# 08_-_Microcontroller.net
KiCad netlist of a schematic drawn in Altium Designer
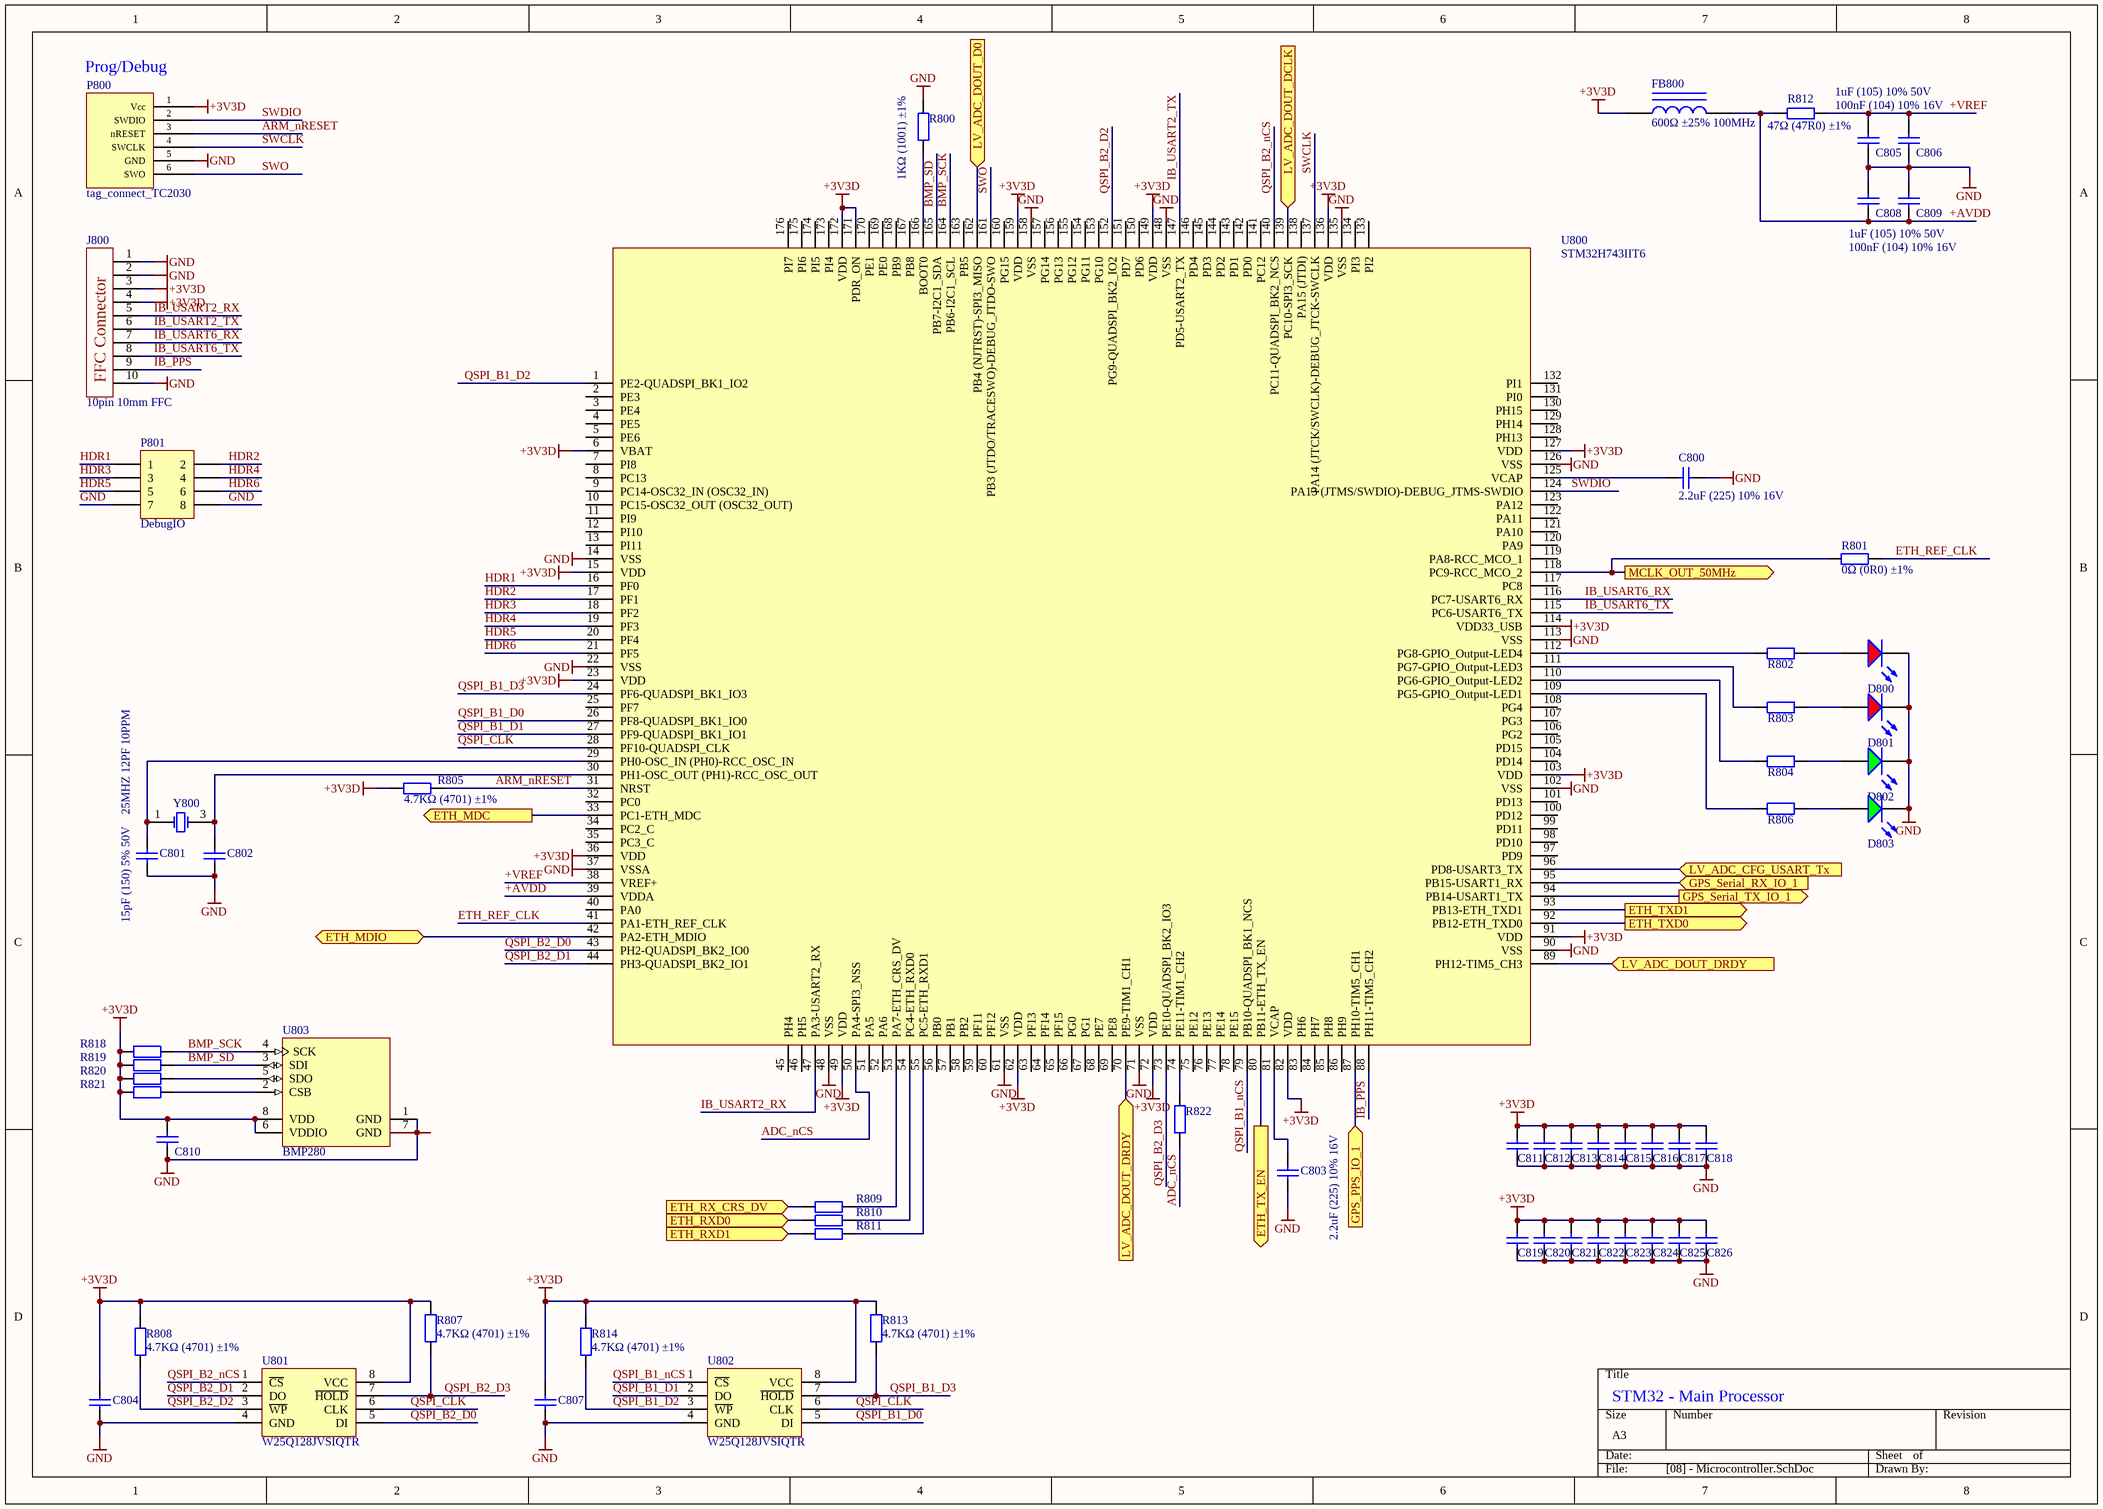
[diagram p0: [08] - Microcontroller.SchDoc]

(export (version "E")
  (design (tool "Eeschema 10.0.6"))
  (components
    (comp (ref "C800")
      (value "2.2uF (225) 10% 16V")
      (footprint "0603_C")
      (description "贴片电容")
      (libsource (lib "Cap") (part "0603 2.2uF (225) 10% 16V"))
    )
    (comp (ref "C801")
      (value "15pF (150) 5% 50V")
      (footprint "0402_C")
      (description "贴片电容")
      (libsource (lib "Cap") (part "0402 15pF (150) 5% 50V"))
    )
    (comp (ref "C802")
      (value "15pF (150) 5% 50V")
      (footprint "0402_C")
      (description "贴片电容")
      (libsource (lib "Cap") (part "0402 15pF (150) 5% 50V"))
    )
    (comp (ref "C803")
      (value "2.2uF (225) 10% 16V")
      (footprint "0603_C")
      (description "贴片电容")
      (libsource (lib "Cap") (part "0603 2.2uF (225) 10% 16V"))
    )
    (comp (ref "C804")
      (value "100nF (104) 10% 16V")
      (footprint "0402_C")
      (description "贴片电容")
      (libsource (lib "Cap") (part "0402 100nF (104) 10% 16V"))
    )
    (comp (ref "C805")
      (value "1uF (105) 10% 50V")
      (footprint "0603_C")
      (description "贴片电容")
      (libsource (lib "Cap") (part "0603 1uF (105) 10% 50V"))
    )
    (comp (ref "C806")
      (value "100nF (104) 10% 16V")
      (footprint "0402_C")
      (description "贴片电容")
      (libsource (lib "Cap") (part "0402 100nF (104) 10% 16V"))
    )
    (comp (ref "C807")
      (value "100nF (104) 10% 16V")
      (footprint "0402_C")
      (description "贴片电容")
      (libsource (lib "Cap") (part "0402 100nF (104) 10% 16V"))
    )
    (comp (ref "C808")
      (value "1uF (105) 10% 50V")
      (footprint "0603_C")
      (description "贴片电容")
      (libsource (lib "Cap") (part "0603 1uF (105) 10% 50V"))
    )
    (comp (ref "C809")
      (value "100nF (104) 10% 16V")
      (footprint "0402_C")
      (description "贴片电容")
      (libsource (lib "Cap") (part "0402 100nF (104) 10% 16V"))
    )
    (comp (ref "C810")
      (value "100nF (104) 10% 16V")
      (footprint "0402_C")
      (description "贴片电容")
      (libsource (lib "Cap") (part "0402 100nF (104) 10% 16V"))
    )
    (comp (ref "C811")
      (value "100nF (104) 10% 16V")
      (footprint "0402_C")
      (description "贴片电容")
      (libsource (lib "Cap") (part "0402 100nF (104) 10% 16V"))
    )
    (comp (ref "C812")
      (value "100nF (104) 10% 16V")
      (footprint "0402_C")
      (description "贴片电容")
      (libsource (lib "Cap") (part "0402 100nF (104) 10% 16V"))
    )
    (comp (ref "C813")
      (value "100nF (104) 10% 16V")
      (footprint "0402_C")
      (description "贴片电容")
      (libsource (lib "Cap") (part "0402 100nF (104) 10% 16V"))
    )
    (comp (ref "C814")
      (value "100nF (104) 10% 16V")
      (footprint "0402_C")
      (description "贴片电容")
      (libsource (lib "Cap") (part "0402 100nF (104) 10% 16V"))
    )
    (comp (ref "C815")
      (value "100nF (104) 10% 16V")
      (footprint "0402_C")
      (description "贴片电容")
      (libsource (lib "Cap") (part "0402 100nF (104) 10% 16V"))
    )
    (comp (ref "C816")
      (value "100nF (104) 10% 16V")
      (footprint "0402_C")
      (description "贴片电容")
      (libsource (lib "Cap") (part "0402 100nF (104) 10% 16V"))
    )
    (comp (ref "C817")
      (value "100nF (104) 10% 16V")
      (footprint "0402_C")
      (description "贴片电容")
      (libsource (lib "Cap") (part "0402 100nF (104) 10% 16V"))
    )
    (comp (ref "C818")
      (value "100nF (104) 10% 16V")
      (footprint "0402_C")
      (description "贴片电容")
      (libsource (lib "Cap") (part "0402 100nF (104) 10% 16V"))
    )
    (comp (ref "C819")
      (value "100nF (104) 10% 16V")
      (footprint "0402_C")
      (description "贴片电容")
      (libsource (lib "Cap") (part "0402 100nF (104) 10% 16V"))
    )
    (comp (ref "C820")
      (value "100nF (104) 10% 16V")
      (footprint "0402_C")
      (description "贴片电容")
      (libsource (lib "Cap") (part "0402 100nF (104) 10% 16V"))
    )
    (comp (ref "C821")
      (value "100nF (104) 10% 16V")
      (footprint "0402_C")
      (description "贴片电容")
      (libsource (lib "Cap") (part "0402 100nF (104) 10% 16V"))
    )
    (comp (ref "C822")
      (value "100nF (104) 10% 16V")
      (footprint "0402_C")
      (description "贴片电容")
      (libsource (lib "Cap") (part "0402 100nF (104) 10% 16V"))
    )
    (comp (ref "C823")
      (value "100nF (104) 10% 16V")
      (footprint "0402_C")
      (description "贴片电容")
      (libsource (lib "Cap") (part "0402 100nF (104) 10% 16V"))
    )
    (comp (ref "C824")
      (value "100nF (104) 10% 16V")
      (footprint "0402_C")
      (description "贴片电容")
      (libsource (lib "Cap") (part "0402 100nF (104) 10% 16V"))
    )
    (comp (ref "C825")
      (value "100nF (104) 10% 16V")
      (footprint "0402_C")
      (description "贴片电容")
      (libsource (lib "Cap") (part "0402 100nF (104) 10% 16V"))
    )
    (comp (ref "C826")
      (value "100nF (104) 10% 16V")
      (footprint "0402_C")
      (description "贴片电容")
      (libsource (lib "Cap") (part "0402 100nF (104) 10% 16V"))
    )
    (comp (ref "D800")
      (value "红灯 0603")
      (footprint "0603_LED_S1")
      (description "发光二极管")
      (libsource (lib "LED") (part "0603 红灯"))
    )
    (comp (ref "D801")
      (value "红灯 0603")
      (footprint "0603_LED_S1")
      (description "发光二极管")
      (libsource (lib "LED") (part "0603 红灯"))
    )
    (comp (ref "D802")
      (value "绿灯 0603")
      (footprint "0603_LED_S1")
      (description "发光二极管")
      (libsource (lib "LED") (part "0603 绿灯"))
    )
    (comp (ref "D803")
      (value "绿灯 0603")
      (footprint "0603_LED_S1")
      (description "发光二极管")
      (libsource (lib "LED") (part "0603 绿灯"))
    )
    (comp (ref "FB800")
      (value "600Ω ±25% 100MHz")
      (footprint "0805_L")
      (description "贴片磁珠")
      (libsource (lib "IUD") (part "0805 600Ω 25% 100MHz"))
    )
    (comp (ref "J800")
      (value "10pin 10mm FFC")
      (footprint "AFA07-S10FCC-00")
      (description "FPC Contact,Bottom 10 0.039\"（1.00mm） 1.0mm FFC, FPC Connectors RoHS")
      (libsource (lib "xPMU_lib") (part "AFA07-S10FCC-00"))
    )
    (comp (ref "P800")
      (value "tag_connect_TC2030")
      (footprint "TC2030-MCP-NL")
      (libsource (lib "FPGA_PMU_lib") (part "tag_connect_TC2030"))
    )
    (comp (ref "P801")
      (value "DebugIO")
      (footprint "HDR2X4")
      (description "Header, 4-Pin, Dual row")
      (fields (field (name "PUBLISHER") "Altium Limited"))
      (libsource (lib "Miscellaneous Connectors") (part "Header 4X2"))
    )
    (comp (ref "R800")
      (value "1KΩ (1001) ±1%")
      (footprint "0402_R")
      (description "贴片电阻")
      (libsource (lib "RES") (part "0402 1KΩ (1001) 1%"))
    )
    (comp (ref "R801")
      (value "0Ω (0R0) ±1%")
      (footprint "0402_R")
      (description "贴片电阻")
      (libsource (lib "") (part "0402 0Ω (0R0) 1%_1"))
    )
    (comp (ref "R802")
      (value "150Ω (1500) ±1%")
      (footprint "0402_R")
      (description "贴片电阻")
      (libsource (lib "RES") (part "0402 150Ω (1500) 1%"))
    )
    (comp (ref "R803")
      (value "150Ω (1500) ±1%")
      (footprint "0402_R")
      (description "贴片电阻")
      (libsource (lib "RES") (part "0402 150Ω (1500) 1%"))
    )
    (comp (ref "R804")
      (value "150Ω (1500) ±1%")
      (footprint "0402_R")
      (description "贴片电阻")
      (libsource (lib "RES") (part "0402 150Ω (1500) 1%"))
    )
    (comp (ref "R805")
      (value "4.7KΩ (4701) ±1%")
      (footprint "0402_R")
      (description "贴片电阻")
      (libsource (lib "") (part "0402 4.7KΩ (4701) 1%_3"))
    )
    (comp (ref "R806")
      (value "150Ω (1500) ±1%")
      (footprint "0402_R")
      (description "贴片电阻")
      (libsource (lib "RES") (part "0402 150Ω (1500) 1%"))
    )
    (comp (ref "R807")
      (value "4.7KΩ (4701) ±1%")
      (footprint "0402_R")
      (description "贴片电阻")
      (libsource (lib "") (part "0402 4.7KΩ (4701) 1%_1"))
    )
    (comp (ref "R808")
      (value "4.7KΩ (4701) ±1%")
      (footprint "0402_R")
      (description "贴片电阻")
      (libsource (lib "") (part "0402 4.7KΩ (4701) 1%_2"))
    )
    (comp (ref "R809")
      (value "49.9Ω (49R9) ±1%")
      (footprint "0402_R")
      (description "贴片电阻")
      (libsource (lib "RES") (part "0402 49.9Ω (49R9) 1%"))
    )
    (comp (ref "R810")
      (value "49.9Ω (49R9) ±1%")
      (footprint "0402_R")
      (description "贴片电阻")
      (libsource (lib "RES") (part "0402 49.9Ω (49R9) 1%"))
    )
    (comp (ref "R811")
      (value "49.9Ω (49R9) ±1%")
      (footprint "0402_R")
      (description "贴片电阻")
      (libsource (lib "RES") (part "0402 49.9Ω (49R9) 1%"))
    )
    (comp (ref "R812")
      (value "47Ω (47R0) ±1%")
      (footprint "0402_R")
      (description "贴片电阻")
      (libsource (lib "RES") (part "0402 47Ω (47R0) 1%"))
    )
    (comp (ref "R813")
      (value "4.7KΩ (4701) ±1%")
      (footprint "0402_R")
      (description "贴片电阻")
      (libsource (lib "") (part "0402 4.7KΩ (4701) 1%_1"))
    )
    (comp (ref "R814")
      (value "4.7KΩ (4701) ±1%")
      (footprint "0402_R")
      (description "贴片电阻")
      (libsource (lib "") (part "0402 4.7KΩ (4701) 1%_2"))
    )
    (comp (ref "R818")
      (value "4.7KΩ (4701) ±1%")
      (footprint "0402_R")
      (description "贴片电阻")
      (libsource (lib "RES") (part "0402 4.7KΩ (4701) 1%"))
    )
    (comp (ref "R819")
      (value "4.7KΩ (4701) ±1%")
      (footprint "0402_R")
      (description "贴片电阻")
      (libsource (lib "RES") (part "0402 4.7KΩ (4701) 1%"))
    )
    (comp (ref "R820")
      (value "4.7KΩ (4701) ±1%")
      (footprint "0402_R")
      (description "贴片电阻")
      (libsource (lib "RES") (part "0402 4.7KΩ (4701) 1%"))
    )
    (comp (ref "R821")
      (value "4.7KΩ (4701) ±1%")
      (footprint "0402_R")
      (description "贴片电阻")
      (libsource (lib "RES") (part "0402 4.7KΩ (4701) 1%"))
    )
    (comp (ref "R822")
      (value "0Ω (0R0) ±1%")
      (footprint "0402_R")
      (description "贴片电阻")
      (libsource (lib "RES") (part "0402 0Ω (0R0) 1%"))
    )
    (comp (ref "U800")
      (value "STM32H743IIT6")
      (footprint "Quad176")
      (description "ST MICROELECTRONICS LQFP-176_24X24X05P ROHS")
      (libsource (lib "xPMU_lib") (part "STM32H743IIT6"))
    )
    (comp (ref "U801")
      (value "W25Q128JVSIQTR")
      (footprint "SOIC-8_208mil")
      (description "Flash ROM")
      (libsource (lib "IC") (part "W25Q128JVSIQTR_[C97521]"))
    )
    (comp (ref "U802")
      (value "W25Q128JVSIQTR")
      (footprint "SOIC-8_208mil")
      (description "Flash ROM")
      (libsource (lib "IC") (part "W25Q128JVSIQTR_[C97521]"))
    )
    (comp (ref "U803")
      (value "BMP280")
      (footprint "BOSC-LGA-8_V_LARGE")
      (description "Digital Pressure Sensor, 1.71 to 3.6 V, -40 to 85 degC, 8-Pin LGA, RoHS, Tape and Reel")
      (fields (field (name "MANUFACTURER") "Bosch Sensortec"))
      (libsource (lib "xPMU_lib") (part "BOSC-BMP280-LGA-8"))
    )
    (comp (ref "Y800")
      (value "25MHZ 12PF 10PPM")
      (footprint "SMD-3225_4P")
      (description "贴片晶振")
      (libsource (lib "CrystalOscillator") (part "SMD-3225_4P  25MHZ 12PF 10PPM"))
    )
  )
  (nets
    (net (code "1") (name "+3V3D") (class "Default")
      (node (ref "C804") (pin "2") (pinfunction "2_2") (pintype "passive"))
      (node (ref "C807") (pin "2") (pinfunction "2_2") (pintype "passive"))
      (node (ref "C810") (pin "2") (pinfunction "2_2") (pintype "passive"))
      (node (ref "C811") (pin "2") (pinfunction "2_2") (pintype "passive"))
      (node (ref "C812") (pin "2") (pinfunction "2_2") (pintype "passive"))
      (node (ref "C813") (pin "2") (pinfunction "2_2") (pintype "passive"))
      (node (ref "C814") (pin "2") (pinfunction "2_2") (pintype "passive"))
      (node (ref "C815") (pin "2") (pinfunction "2_2") (pintype "passive"))
      (node (ref "C816") (pin "2") (pinfunction "2_2") (pintype "passive"))
      (node (ref "C817") (pin "2") (pinfunction "2_2") (pintype "passive"))
      (node (ref "C818") (pin "2") (pinfunction "2_2") (pintype "passive"))
      (node (ref "C819") (pin "2") (pinfunction "2_2") (pintype "passive"))
      (node (ref "C820") (pin "2") (pinfunction "2_2") (pintype "passive"))
      (node (ref "C821") (pin "2") (pinfunction "2_2") (pintype "passive"))
      (node (ref "C822") (pin "2") (pinfunction "2_2") (pintype "passive"))
      (node (ref "C823") (pin "2") (pinfunction "2_2") (pintype "passive"))
      (node (ref "C824") (pin "2") (pinfunction "2_2") (pintype "passive"))
      (node (ref "C825") (pin "2") (pinfunction "2_2") (pintype "passive"))
      (node (ref "C826") (pin "2") (pinfunction "2_2") (pintype "passive"))
      (node (ref "FB800") (pin "1") (pinfunction "1_1") (pintype "passive"))
      (node (ref "J800") (pin "3") (pinfunction "3_3") (pintype "passive"))
      (node (ref "J800") (pin "4") (pinfunction "4_4") (pintype "passive"))
      (node (ref "P800") (pin "1") (pinfunction "Vcc_1") (pintype "passive"))
      (node (ref "R805") (pin "2") (pinfunction "2_2") (pintype "passive"))
      (node (ref "R807") (pin "2") (pinfunction "2_2") (pintype "passive"))
      (node (ref "R808") (pin "1") (pinfunction "1_1") (pintype "passive"))
      (node (ref "R813") (pin "2") (pinfunction "2_2") (pintype "passive"))
      (node (ref "R814") (pin "1") (pinfunction "1_1") (pintype "passive"))
      (node (ref "R818") (pin "1") (pinfunction "1_1") (pintype "passive"))
      (node (ref "R819") (pin "1") (pinfunction "1_1") (pintype "passive"))
      (node (ref "R820") (pin "1") (pinfunction "1_1") (pintype "passive"))
      (node (ref "R821") (pin "1") (pinfunction "1_1") (pintype "passive"))
      (node (ref "U800") (pin "103") (pinfunction "VDD_103") (pintype "passive"))
      (node (ref "U800") (pin "114") (pinfunction "VDD33_USB_114") (pintype "passive"))
      (node (ref "U800") (pin "127") (pinfunction "VDD_127") (pintype "passive"))
      (node (ref "U800") (pin "136") (pinfunction "VDD_136") (pintype "passive"))
      (node (ref "U800") (pin "149") (pinfunction "VDD_149") (pintype "passive"))
      (node (ref "U800") (pin "15") (pinfunction "VDD_15") (pintype "passive"))
      (node (ref "U800") (pin "159") (pinfunction "VDD_159") (pintype "passive"))
      (node (ref "U800") (pin "171") (pinfunction "PDR_ON_171") (pintype "passive"))
      (node (ref "U800") (pin "172") (pinfunction "VDD_172") (pintype "passive"))
      (node (ref "U800") (pin "23") (pinfunction "VDD_23") (pintype "passive"))
      (node (ref "U800") (pin "36") (pinfunction "VDD_36") (pintype "passive"))
      (node (ref "U800") (pin "49") (pinfunction "VDD_49") (pintype "passive"))
      (node (ref "U800") (pin "6") (pinfunction "VBAT_6") (pintype "passive"))
      (node (ref "U800") (pin "62") (pinfunction "VDD_62") (pintype "passive"))
      (node (ref "U800") (pin "72") (pinfunction "VDD_72") (pintype "passive"))
      (node (ref "U800") (pin "82") (pinfunction "VDD_82") (pintype "passive"))
      (node (ref "U800") (pin "91") (pinfunction "VDD_91") (pintype "passive"))
      (node (ref "U801") (pin "8") (pinfunction "VCC_8") (pintype "passive"))
      (node (ref "U802") (pin "8") (pinfunction "VCC_8") (pintype "passive"))
      (node (ref "U803") (pin "6") (pinfunction "VDDIO_6") (pintype "power_in"))
      (node (ref "U803") (pin "8") (pinfunction "VDD_8") (pintype "power_in"))
    )
    (net (code "2") (name "/+AVDD") (class "Default")
      (node (ref "C808") (pin "1") (pinfunction "1_1") (pintype "passive"))
      (node (ref "C809") (pin "1") (pinfunction "1_1") (pintype "passive"))
      (node (ref "FB800") (pin "2") (pinfunction "2_2") (pintype "passive"))
      (node (ref "R812") (pin "1") (pinfunction "1_1") (pintype "passive"))
      (node (ref "U800") (pin "39") (pinfunction "VDDA_39") (pintype "passive"))
    )
    (net (code "3") (name "/+VREF") (class "Default")
      (node (ref "C805") (pin "2") (pinfunction "2_2") (pintype "passive"))
      (node (ref "C806") (pin "2") (pinfunction "2_2") (pintype "passive"))
      (node (ref "R812") (pin "2") (pinfunction "2_2") (pintype "passive"))
      (node (ref "U800") (pin "38") (pinfunction "VREF+_38") (pintype "passive"))
    )
    (net (code "4") (name "/ADC_nCS") (class "Default")
      (node (ref "R822") (pin "1") (pinfunction "1_1") (pintype "passive"))
      (node (ref "U800") (pin "50") (pinfunction "PA4-SPI3_NSS_50") (pintype "passive"))
    )
    (net (code "5") (name "/ARM_nRESET") (class "Default")
      (node (ref "P800") (pin "3") (pinfunction "nRESET_3") (pintype "passive"))
      (node (ref "R805") (pin "1") (pinfunction "1_1") (pintype "passive"))
      (node (ref "U800") (pin "31") (pinfunction "NRST_31") (pintype "passive"))
    )
    (net (code "6") (name "/BMP_SCK") (class "Default")
      (node (ref "R818") (pin "2") (pinfunction "2_2") (pintype "passive"))
      (node (ref "U800") (pin "164") (pinfunction "PB6-I2C1_SCL_164") (pintype "passive"))
      (node (ref "U803") (pin "4") (pinfunction "SCK_4") (pintype "input"))
    )
    (net (code "7") (name "/BMP_SD") (class "Default")
      (node (ref "R819") (pin "2") (pinfunction "2_2") (pintype "passive"))
      (node (ref "U800") (pin "165") (pinfunction "PB7-I2C1_SDA_165") (pintype "passive"))
      (node (ref "U803") (pin "3") (pinfunction "SDI_3") (pintype "bidirectional"))
    )
    (net (code "8") (name "/ETH_MDC") (class "Default")
      (node (ref "U800") (pin "33") (pinfunction "PC1-ETH_MDC_33") (pintype "passive"))
    )
    (net (code "9") (name "/ETH_MDIO") (class "Default")
      (node (ref "U800") (pin "42") (pinfunction "PA2-ETH_MDIO_42") (pintype "passive"))
    )
    (net (code "10") (name "/ETH_REF_CLK") (class "Default")
      (node (ref "R801") (pin "2") (pinfunction "2_2") (pintype "passive"))
      (node (ref "U800") (pin "41") (pinfunction "PA1-ETH_REF_CLK_41") (pintype "passive"))
    )
    (net (code "11") (name "/ETH_RXD0") (class "Default")
      (node (ref "R810") (pin "1") (pinfunction "1_1") (pintype "passive"))
    )
    (net (code "12") (name "/ETH_RXD1") (class "Default")
      (node (ref "R811") (pin "1") (pinfunction "1_1") (pintype "passive"))
    )
    (net (code "13") (name "/ETH_RX_CRS_DV") (class "Default")
      (node (ref "R809") (pin "1") (pinfunction "1_1") (pintype "passive"))
    )
    (net (code "14") (name "/ETH_TXD0") (class "Default")
      (node (ref "U800") (pin "92") (pinfunction "PB12-ETH_TXD0_92") (pintype "passive"))
    )
    (net (code "15") (name "/ETH_TXD1") (class "Default")
      (node (ref "U800") (pin "93") (pinfunction "PB13-ETH_TXD1_93") (pintype "passive"))
    )
    (net (code "16") (name "/ETH_TX_EN") (class "Default")
      (node (ref "U800") (pin "80") (pinfunction "PB11-ETH_TX_EN_80") (pintype "passive"))
    )
    (net (code "17") (name "/GPS_PPS_IO_1") (class "Default")
      (node (ref "U800") (pin "87") (pinfunction "PH10-TIM5_CH1_87") (pintype "passive"))
    )
    (net (code "18") (name "/GPS_Serial_RX_IO_1") (class "Default")
      (node (ref "U800") (pin "95") (pinfunction "PB15-USART1_RX_95") (pintype "passive"))
    )
    (net (code "19") (name "/GPS_Serial_TX_IO_1") (class "Default")
      (node (ref "U800") (pin "94") (pinfunction "PB14-USART1_TX_94") (pintype "passive"))
    )
    (net (code "20") (name "/HDR1") (class "Default")
      (node (ref "P801") (pin "1") (pinfunction "1_1") (pintype "passive"))
      (node (ref "U800") (pin "16") (pinfunction "PF0_16") (pintype "passive"))
    )
    (net (code "21") (name "/HDR2") (class "Default")
      (node (ref "P801") (pin "2") (pinfunction "2_2") (pintype "passive"))
      (node (ref "U800") (pin "17") (pinfunction "PF1_17") (pintype "passive"))
    )
    (net (code "22") (name "/HDR3") (class "Default")
      (node (ref "P801") (pin "3") (pinfunction "3_3") (pintype "passive"))
      (node (ref "U800") (pin "18") (pinfunction "PF2_18") (pintype "passive"))
    )
    (net (code "23") (name "/HDR4") (class "Default")
      (node (ref "P801") (pin "4") (pinfunction "4_4") (pintype "passive"))
      (node (ref "U800") (pin "19") (pinfunction "PF3_19") (pintype "passive"))
    )
    (net (code "24") (name "/HDR5") (class "Default")
      (node (ref "P801") (pin "5") (pinfunction "5_5") (pintype "passive"))
      (node (ref "U800") (pin "20") (pinfunction "PF4_20") (pintype "passive"))
    )
    (net (code "25") (name "/HDR6") (class "Default")
      (node (ref "P801") (pin "6") (pinfunction "6_6") (pintype "passive"))
      (node (ref "U800") (pin "21") (pinfunction "PF5_21") (pintype "passive"))
    )
    (net (code "26") (name "/IB_PPS") (class "Default")
      (node (ref "J800") (pin "9") (pinfunction "9_9") (pintype "passive"))
      (node (ref "U800") (pin "88") (pinfunction "PH11-TIM5_CH2_88") (pintype "passive"))
    )
    (net (code "27") (name "/IB_USART2_RX") (class "Default")
      (node (ref "J800") (pin "5") (pinfunction "5_5") (pintype "passive"))
      (node (ref "U800") (pin "47") (pinfunction "PA3-USART2_RX_47") (pintype "passive"))
    )
    (net (code "28") (name "/IB_USART2_TX") (class "Default")
      (node (ref "J800") (pin "6") (pinfunction "6_6") (pintype "passive"))
      (node (ref "U800") (pin "147") (pinfunction "PD5-USART2_TX_147") (pintype "passive"))
    )
    (net (code "29") (name "/IB_USART6_RX") (class "Default")
      (node (ref "J800") (pin "7") (pinfunction "7_7") (pintype "passive"))
      (node (ref "U800") (pin "116") (pinfunction "PC7-USART6_RX_116") (pintype "passive"))
    )
    (net (code "30") (name "/IB_USART6_TX") (class "Default")
      (node (ref "J800") (pin "8") (pinfunction "8_8") (pintype "passive"))
      (node (ref "U800") (pin "115") (pinfunction "PC6-USART6_TX_115") (pintype "passive"))
    )
    (net (code "31") (name "/LV_ADC_CFG_USART_Tx") (class "Default")
      (node (ref "U800") (pin "96") (pinfunction "PD8-USART3_TX_96") (pintype "passive"))
    )
    (net (code "32") (name "/LV_ADC_DOUT_D0") (class "Default")
      (node (ref "U800") (pin "162") (pinfunction "PB4_(NJTRST)-SPI3_MISO_162") (pintype "passive"))
    )
    (net (code "33") (name "/LV_ADC_DOUT_DCLK") (class "Default")
      (node (ref "U800") (pin "139") (pinfunction "PC10-SPI3_SCK_139") (pintype "passive"))
    )
    (net (code "34") (name "/LV_ADC_DOUT_DRDY") (class "Default")
      (node (ref "U800") (pin "70") (pinfunction "PE9-TIM1_CH1_70") (pintype "passive"))
      (node (ref "U800") (pin "89") (pinfunction "PH12-TIM5_CH3_89") (pintype "passive"))
    )
    (net (code "35") (name "/MCLK_OUT_50MHz") (class "Default")
      (node (ref "R801") (pin "1") (pinfunction "1_1") (pintype "passive"))
      (node (ref "U800") (pin "118") (pinfunction "PC9-RCC_MCO_2_118") (pintype "passive"))
    )
    (net (code "36") (name "/QSPI_B1_D0") (class "Default")
      (node (ref "U800") (pin "26") (pinfunction "PF8-QUADSPI_BK1_IO0_26") (pintype "passive"))
      (node (ref "U802") (pin "5") (pinfunction "DI_5") (pintype "passive"))
    )
    (net (code "37") (name "/QSPI_B1_D1") (class "Default")
      (node (ref "U800") (pin "27") (pinfunction "PF9-QUADSPI_BK1_IO1_27") (pintype "passive"))
      (node (ref "U802") (pin "2") (pinfunction "DO_2") (pintype "passive"))
    )
    (net (code "38") (name "/QSPI_B1_D2") (class "Default")
      (node (ref "R814") (pin "2") (pinfunction "2_2") (pintype "passive"))
      (node (ref "U800") (pin "1") (pinfunction "PE2-QUADSPI_BK1_IO2_1") (pintype "passive"))
      (node (ref "U802") (pin "3") (pinfunction "~{WP}_3") (pintype "passive"))
    )
    (net (code "39") (name "/QSPI_B1_D3") (class "Default")
      (node (ref "R813") (pin "1") (pinfunction "1_1") (pintype "passive"))
      (node (ref "U800") (pin "24") (pinfunction "PF6-QUADSPI_BK1_IO3_24") (pintype "passive"))
      (node (ref "U802") (pin "7") (pinfunction "~{HOLD}_7") (pintype "passive"))
    )
    (net (code "40") (name "/QSPI_B1_nCS") (class "Default")
      (node (ref "U800") (pin "79") (pinfunction "PB10-QUADSPI_BK1_NCS_79") (pintype "passive"))
      (node (ref "U802") (pin "1") (pinfunction "~{CS}_1") (pintype "passive"))
    )
    (net (code "41") (name "/QSPI_B2_D0") (class "Default")
      (node (ref "U800") (pin "43") (pinfunction "PH2-QUADSPI_BK2_IO0_43") (pintype "passive"))
      (node (ref "U801") (pin "5") (pinfunction "DI_5") (pintype "passive"))
    )
    (net (code "42") (name "/QSPI_B2_D1") (class "Default")
      (node (ref "U800") (pin "44") (pinfunction "PH3-QUADSPI_BK2_IO1_44") (pintype "passive"))
      (node (ref "U801") (pin "2") (pinfunction "DO_2") (pintype "passive"))
    )
    (net (code "43") (name "/QSPI_B2_D2") (class "Default")
      (node (ref "R808") (pin "2") (pinfunction "2_2") (pintype "passive"))
      (node (ref "U800") (pin "152") (pinfunction "PG9-QUADSPI_BK2_IO2_152") (pintype "passive"))
      (node (ref "U801") (pin "3") (pinfunction "~{WP}_3") (pintype "passive"))
    )
    (net (code "44") (name "/QSPI_B2_D3") (class "Default")
      (node (ref "R807") (pin "1") (pinfunction "1_1") (pintype "passive"))
      (node (ref "U800") (pin "73") (pinfunction "PE10-QUADSPI_BK2_IO3_73") (pintype "passive"))
      (node (ref "U801") (pin "7") (pinfunction "~{HOLD}_7") (pintype "passive"))
    )
    (net (code "45") (name "/QSPI_B2_nCS") (class "Default")
      (node (ref "U800") (pin "140") (pinfunction "PC11-QUADSPI_BK2_NCS_140") (pintype "passive"))
      (node (ref "U801") (pin "1") (pinfunction "~{CS}_1") (pintype "passive"))
    )
    (net (code "46") (name "/QSPI_CLK") (class "Default")
      (node (ref "U800") (pin "28") (pinfunction "PF10-QUADSPI_CLK_28") (pintype "passive"))
      (node (ref "U801") (pin "6") (pinfunction "CLK_6") (pintype "passive"))
      (node (ref "U802") (pin "6") (pinfunction "CLK_6") (pintype "passive"))
    )
    (net (code "47") (name "/SWCLK") (class "Default")
      (node (ref "P800") (pin "4") (pinfunction "SWCLK_4") (pintype "passive"))
      (node (ref "U800") (pin "137") (pinfunction "PA14_(JTCK/SWCLK)-DEBUG_JTCK-SWCLK_137") (pintype "passive"))
    )
    (net (code "48") (name "/SWDIO") (class "Default")
      (node (ref "P800") (pin "2") (pinfunction "SWDIO_2") (pintype "passive"))
      (node (ref "U800") (pin "124") (pinfunction "PA13_(JTMS/SWDIO)-DEBUG_JTMS-SWDIO_124") (pintype "passive"))
    )
    (net (code "49") (name "/SWO") (class "Default")
      (node (ref "P800") (pin "6") (pinfunction "SWO_6") (pintype "passive"))
      (node (ref "U800") (pin "161") (pinfunction "PB3_(JTDO/TRACESWO)-DEBUG_JTDO-SWO_161") (pintype "passive"))
    )
    (net (code "50") (name "GND") (class "Default")
      (node (ref "C800") (pin "2") (pinfunction "2_2") (pintype "passive"))
      (node (ref "C801") (pin "1") (pinfunction "1_1") (pintype "passive"))
      (node (ref "C802") (pin "1") (pinfunction "1_1") (pintype "passive"))
      (node (ref "C803") (pin "2") (pinfunction "2_2") (pintype "passive"))
      (node (ref "C804") (pin "1") (pinfunction "1_1") (pintype "passive"))
      (node (ref "C805") (pin "1") (pinfunction "1_1") (pintype "passive"))
      (node (ref "C806") (pin "1") (pinfunction "1_1") (pintype "passive"))
      (node (ref "C807") (pin "1") (pinfunction "1_1") (pintype "passive"))
      (node (ref "C808") (pin "2") (pinfunction "2_2") (pintype "passive"))
      (node (ref "C809") (pin "2") (pinfunction "2_2") (pintype "passive"))
      (node (ref "C810") (pin "1") (pinfunction "1_1") (pintype "passive"))
      (node (ref "C811") (pin "1") (pinfunction "1_1") (pintype "passive"))
      (node (ref "C812") (pin "1") (pinfunction "1_1") (pintype "passive"))
      (node (ref "C813") (pin "1") (pinfunction "1_1") (pintype "passive"))
      (node (ref "C814") (pin "1") (pinfunction "1_1") (pintype "passive"))
      (node (ref "C815") (pin "1") (pinfunction "1_1") (pintype "passive"))
      (node (ref "C816") (pin "1") (pinfunction "1_1") (pintype "passive"))
      (node (ref "C817") (pin "1") (pinfunction "1_1") (pintype "passive"))
      (node (ref "C818") (pin "1") (pinfunction "1_1") (pintype "passive"))
      (node (ref "C819") (pin "1") (pinfunction "1_1") (pintype "passive"))
      (node (ref "C820") (pin "1") (pinfunction "1_1") (pintype "passive"))
      (node (ref "C821") (pin "1") (pinfunction "1_1") (pintype "passive"))
      (node (ref "C822") (pin "1") (pinfunction "1_1") (pintype "passive"))
      (node (ref "C823") (pin "1") (pinfunction "1_1") (pintype "passive"))
      (node (ref "C824") (pin "1") (pinfunction "1_1") (pintype "passive"))
      (node (ref "C825") (pin "1") (pinfunction "1_1") (pintype "passive"))
      (node (ref "C826") (pin "1") (pinfunction "1_1") (pintype "passive"))
      (node (ref "D800") (pin "K") (pinfunction "K_K") (pintype "passive"))
      (node (ref "D801") (pin "K") (pinfunction "K_K") (pintype "passive"))
      (node (ref "D802") (pin "K") (pinfunction "K_K") (pintype "passive"))
      (node (ref "D803") (pin "K") (pinfunction "K_K") (pintype "passive"))
      (node (ref "J800") (pin "1") (pinfunction "1_1") (pintype "passive"))
      (node (ref "J800") (pin "10") (pinfunction "10_10") (pintype "passive"))
      (node (ref "J800") (pin "2") (pinfunction "2_2") (pintype "passive"))
      (node (ref "P800") (pin "5") (pinfunction "GND_5") (pintype "passive"))
      (node (ref "P801") (pin "7") (pinfunction "7_7") (pintype "passive"))
      (node (ref "P801") (pin "8") (pinfunction "8_8") (pintype "passive"))
      (node (ref "R800") (pin "2") (pinfunction "2_2") (pintype "passive"))
      (node (ref "U800") (pin "102") (pinfunction "VSS_102") (pintype "passive"))
      (node (ref "U800") (pin "113") (pinfunction "VSS_113") (pintype "passive"))
      (node (ref "U800") (pin "126") (pinfunction "VSS_126") (pintype "passive"))
      (node (ref "U800") (pin "135") (pinfunction "VSS_135") (pintype "passive"))
      (node (ref "U800") (pin "14") (pinfunction "VSS_14") (pintype "passive"))
      (node (ref "U800") (pin "148") (pinfunction "VSS_148") (pintype "passive"))
      (node (ref "U800") (pin "158") (pinfunction "VSS_158") (pintype "passive"))
      (node (ref "U800") (pin "22") (pinfunction "VSS_22") (pintype "passive"))
      (node (ref "U800") (pin "37") (pinfunction "VSSA_37") (pintype "passive"))
      (node (ref "U800") (pin "48") (pinfunction "VSS_48") (pintype "passive"))
      (node (ref "U800") (pin "61") (pinfunction "VSS_61") (pintype "passive"))
      (node (ref "U800") (pin "71") (pinfunction "VSS_71") (pintype "passive"))
      (node (ref "U800") (pin "90") (pinfunction "VSS_90") (pintype "passive"))
      (node (ref "U801") (pin "4") (pinfunction "GND_4") (pintype "passive"))
      (node (ref "U802") (pin "4") (pinfunction "GND_4") (pintype "passive"))
      (node (ref "U803") (pin "1") (pinfunction "GND_1") (pintype "power_in"))
      (node (ref "U803") (pin "7") (pinfunction "GND_7") (pintype "power_in"))
    )
    (net (code "51") (name "Net-(C800-Pad1)") (class "Default")
      (node (ref "C800") (pin "1") (pinfunction "1_1") (pintype "passive"))
      (node (ref "U800") (pin "125") (pinfunction "VCAP_125") (pintype "passive"))
    )
    (net (code "52") (name "Net-(C803-Pad1)") (class "Default")
      (node (ref "C803") (pin "1") (pinfunction "1_1") (pintype "passive"))
      (node (ref "U800") (pin "81") (pinfunction "VCAP_81") (pintype "passive"))
    )
    (net (code "53") (name "Net-(D800-PadA)") (class "Default")
      (node (ref "D800") (pin "A") (pinfunction "A_A") (pintype "passive"))
      (node (ref "R802") (pin "1") (pinfunction "1_1") (pintype "passive"))
    )
    (net (code "54") (name "Net-(D801-PadA)") (class "Default")
      (node (ref "D801") (pin "A") (pinfunction "A_A") (pintype "passive"))
      (node (ref "R803") (pin "1") (pinfunction "1_1") (pintype "passive"))
    )
    (net (code "55") (name "Net-(D802-PadA)") (class "Default")
      (node (ref "D802") (pin "A") (pinfunction "A_A") (pintype "passive"))
      (node (ref "R804") (pin "1") (pinfunction "1_1") (pintype "passive"))
    )
    (net (code "56") (name "Net-(D803-PadA)") (class "Default")
      (node (ref "D803") (pin "A") (pinfunction "A_A") (pintype "passive"))
      (node (ref "R806") (pin "1") (pinfunction "1_1") (pintype "passive"))
    )
    (net (code "57") (name "Net-(U800-BOOT0)") (class "Default")
      (node (ref "R800") (pin "1") (pinfunction "1_1") (pintype "passive"))
      (node (ref "U800") (pin "166") (pinfunction "BOOT0_166") (pintype "passive"))
    )
    (net (code "58") (name "Net-(U800-PA7-ETH_CRS_DV)") (class "Default")
      (node (ref "R809") (pin "2") (pinfunction "2_2") (pintype "passive"))
      (node (ref "U800") (pin "53") (pinfunction "PA7-ETH_CRS_DV_53") (pintype "passive"))
    )
    (net (code "59") (name "Net-(U800-PC4-ETH_RXD0)") (class "Default")
      (node (ref "R810") (pin "2") (pinfunction "2_2") (pintype "passive"))
      (node (ref "U800") (pin "54") (pinfunction "PC4-ETH_RXD0_54") (pintype "passive"))
    )
    (net (code "60") (name "Net-(U800-PC5-ETH_RXD1)") (class "Default")
      (node (ref "R811") (pin "2") (pinfunction "2_2") (pintype "passive"))
      (node (ref "U800") (pin "55") (pinfunction "PC5-ETH_RXD1_55") (pintype "passive"))
    )
    (net (code "61") (name "Net-(U800-PE11-TIM1_CH2)") (class "Default")
      (node (ref "R822") (pin "2") (pinfunction "2_2") (pintype "passive"))
      (node (ref "U800") (pin "74") (pinfunction "PE11-TIM1_CH2_74") (pintype "passive"))
    )
    (net (code "62") (name "Net-(U800-PG5-GPIO_Output-LED1)") (class "Default")
      (node (ref "R806") (pin "2") (pinfunction "2_2") (pintype "passive"))
      (node (ref "U800") (pin "109") (pinfunction "PG5-GPIO_Output-LED1_109") (pintype "passive"))
    )
    (net (code "63") (name "Net-(U800-PG6-GPIO_Output-LED2)") (class "Default")
      (node (ref "R804") (pin "2") (pinfunction "2_2") (pintype "passive"))
      (node (ref "U800") (pin "110") (pinfunction "PG6-GPIO_Output-LED2_110") (pintype "passive"))
    )
    (net (code "64") (name "Net-(U800-PG7-GPIO_Output-LED3)") (class "Default")
      (node (ref "R803") (pin "2") (pinfunction "2_2") (pintype "passive"))
      (node (ref "U800") (pin "111") (pinfunction "PG7-GPIO_Output-LED3_111") (pintype "passive"))
    )
    (net (code "65") (name "Net-(U800-PG8-GPIO_Output-LED4)") (class "Default")
      (node (ref "R802") (pin "2") (pinfunction "2_2") (pintype "passive"))
      (node (ref "U800") (pin "112") (pinfunction "PG8-GPIO_Output-LED4_112") (pintype "passive"))
    )
    (net (code "66") (name "Net-(U800-PH0-OSC_IN_(PH0)-RCC_OSC_IN)") (class "Default")
      (node (ref "C801") (pin "2") (pinfunction "2_2") (pintype "passive"))
      (node (ref "U800") (pin "29") (pinfunction "PH0-OSC_IN_(PH0)-RCC_OSC_IN_29") (pintype "passive"))
      (node (ref "Y800") (pin "1") (pinfunction "OSC1_1") (pintype "passive"))
    )
    (net (code "67") (name "Net-(U800-PH1-OSC_OUT_(PH1)-RCC_OSC_OUT)") (class "Default")
      (node (ref "C802") (pin "2") (pinfunction "2_2") (pintype "passive"))
      (node (ref "U800") (pin "30") (pinfunction "PH1-OSC_OUT_(PH1)-RCC_OSC_OUT_30") (pintype "passive"))
      (node (ref "Y800") (pin "3") (pinfunction "OSC2_3") (pintype "passive"))
    )
    (net (code "68") (name "Net-(U803-CSB)") (class "Default")
      (node (ref "R821") (pin "2") (pinfunction "2_2") (pintype "passive"))
      (node (ref "U803") (pin "2") (pinfunction "CSB_2") (pintype "input"))
    )
    (net (code "69") (name "Net-(U803-SDO)") (class "Default")
      (node (ref "R820") (pin "2") (pinfunction "2_2") (pintype "passive"))
      (node (ref "U803") (pin "5") (pinfunction "SDO_5") (pintype "bidirectional"))
    )
    (net (code "70") (name "unconnected-(U800-PA0-Pad40)") (class "Default")
      (node (ref "U800") (pin "40") (pinfunction "PA0_40") (pintype "passive"))
    )
    (net (code "71") (name "unconnected-(U800-PA5-Pad51)") (class "Default")
      (node (ref "U800") (pin "51") (pinfunction "PA5_51") (pintype "passive"))
    )
    (net (code "72") (name "unconnected-(U800-PA6-Pad52)") (class "Default")
      (node (ref "U800") (pin "52") (pinfunction "PA6_52") (pintype "passive"))
    )
    (net (code "73") (name "unconnected-(U800-PA8-RCC_MCO_1-Pad119)") (class "Default")
      (node (ref "U800") (pin "119") (pinfunction "PA8-RCC_MCO_1_119") (pintype "passive"))
    )
    (net (code "74") (name "unconnected-(U800-PA9-Pad120)") (class "Default")
      (node (ref "U800") (pin "120") (pinfunction "PA9_120") (pintype "passive"))
    )
    (net (code "75") (name "unconnected-(U800-PA10-Pad121)") (class "Default")
      (node (ref "U800") (pin "121") (pinfunction "PA10_121") (pintype "passive"))
    )
    (net (code "76") (name "unconnected-(U800-PA11-Pad122)") (class "Default")
      (node (ref "U800") (pin "122") (pinfunction "PA11_122") (pintype "passive"))
    )
    (net (code "77") (name "unconnected-(U800-PA12-Pad123)") (class "Default")
      (node (ref "U800") (pin "123") (pinfunction "PA12_123") (pintype "passive"))
    )
    (net (code "78") (name "unconnected-(U800-PA15_(JTDI)-Pad138)") (class "Default")
      (node (ref "U800") (pin "138") (pinfunction "PA15_(JTDI)_138") (pintype "passive"))
    )
    (net (code "79") (name "unconnected-(U800-PB0-Pad56)") (class "Default")
      (node (ref "U800") (pin "56") (pinfunction "PB0_56") (pintype "passive"))
    )
    (net (code "80") (name "unconnected-(U800-PB1-Pad57)") (class "Default")
      (node (ref "U800") (pin "57") (pinfunction "PB1_57") (pintype "passive"))
    )
    (net (code "81") (name "unconnected-(U800-PB2-Pad58)") (class "Default")
      (node (ref "U800") (pin "58") (pinfunction "PB2_58") (pintype "passive"))
    )
    (net (code "82") (name "unconnected-(U800-PB5-Pad163)") (class "Default")
      (node (ref "U800") (pin "163") (pinfunction "PB5_163") (pintype "passive"))
    )
    (net (code "83") (name "unconnected-(U800-PB8-Pad167)") (class "Default")
      (node (ref "U800") (pin "167") (pinfunction "PB8_167") (pintype "passive"))
    )
    (net (code "84") (name "unconnected-(U800-PB9-Pad168)") (class "Default")
      (node (ref "U800") (pin "168") (pinfunction "PB9_168") (pintype "passive"))
    )
    (net (code "85") (name "unconnected-(U800-PC0-Pad32)") (class "Default")
      (node (ref "U800") (pin "32") (pinfunction "PC0_32") (pintype "passive"))
    )
    (net (code "86") (name "unconnected-(U800-PC2_C-Pad34)") (class "Default")
      (node (ref "U800") (pin "34") (pinfunction "PC2_C_34") (pintype "passive"))
    )
    (net (code "87") (name "unconnected-(U800-PC3_C-Pad35)") (class "Default")
      (node (ref "U800") (pin "35") (pinfunction "PC3_C_35") (pintype "passive"))
    )
    (net (code "88") (name "unconnected-(U800-PC8-Pad117)") (class "Default")
      (node (ref "U800") (pin "117") (pinfunction "PC8_117") (pintype "passive"))
    )
    (net (code "89") (name "unconnected-(U800-PC12-Pad141)") (class "Default")
      (node (ref "U800") (pin "141") (pinfunction "PC12_141") (pintype "passive"))
    )
    (net (code "90") (name "unconnected-(U800-PC13-Pad8)") (class "Default")
      (node (ref "U800") (pin "8") (pinfunction "PC13_8") (pintype "passive"))
    )
    (net (code "91") (name "unconnected-(U800-PC14-OSC32_IN_(OSC32_IN)-Pad9)") (class "Default")
      (node (ref "U800") (pin "9") (pinfunction "PC14-OSC32_IN_(OSC32_IN)_9") (pintype "passive"))
    )
    (net (code "92") (name "unconnected-(U800-PC15-OSC32_OUT_(OSC32_OUT)-Pad10)") (class "Default")
      (node (ref "U800") (pin "10") (pinfunction "PC15-OSC32_OUT_(OSC32_OUT)_10") (pintype "passive"))
    )
    (net (code "93") (name "unconnected-(U800-PD0-Pad142)") (class "Default")
      (node (ref "U800") (pin "142") (pinfunction "PD0_142") (pintype "passive"))
    )
    (net (code "94") (name "unconnected-(U800-PD1-Pad143)") (class "Default")
      (node (ref "U800") (pin "143") (pinfunction "PD1_143") (pintype "passive"))
    )
    (net (code "95") (name "unconnected-(U800-PD2-Pad144)") (class "Default")
      (node (ref "U800") (pin "144") (pinfunction "PD2_144") (pintype "passive"))
    )
    (net (code "96") (name "unconnected-(U800-PD3-Pad145)") (class "Default")
      (node (ref "U800") (pin "145") (pinfunction "PD3_145") (pintype "passive"))
    )
    (net (code "97") (name "unconnected-(U800-PD4-Pad146)") (class "Default")
      (node (ref "U800") (pin "146") (pinfunction "PD4_146") (pintype "passive"))
    )
    (net (code "98") (name "unconnected-(U800-PD6-Pad150)") (class "Default")
      (node (ref "U800") (pin "150") (pinfunction "PD6_150") (pintype "passive"))
    )
    (net (code "99") (name "unconnected-(U800-PD7-Pad151)") (class "Default")
      (node (ref "U800") (pin "151") (pinfunction "PD7_151") (pintype "passive"))
    )
    (net (code "100") (name "unconnected-(U800-PD9-Pad97)") (class "Default")
      (node (ref "U800") (pin "97") (pinfunction "PD9_97") (pintype "passive"))
    )
    (net (code "101") (name "unconnected-(U800-PD10-Pad98)") (class "Default")
      (node (ref "U800") (pin "98") (pinfunction "PD10_98") (pintype "passive"))
    )
    (net (code "102") (name "unconnected-(U800-PD11-Pad99)") (class "Default")
      (node (ref "U800") (pin "99") (pinfunction "PD11_99") (pintype "passive"))
    )
    (net (code "103") (name "unconnected-(U800-PD12-Pad100)") (class "Default")
      (node (ref "U800") (pin "100") (pinfunction "PD12_100") (pintype "passive"))
    )
    (net (code "104") (name "unconnected-(U800-PD13-Pad101)") (class "Default")
      (node (ref "U800") (pin "101") (pinfunction "PD13_101") (pintype "passive"))
    )
    (net (code "105") (name "unconnected-(U800-PD14-Pad104)") (class "Default")
      (node (ref "U800") (pin "104") (pinfunction "PD14_104") (pintype "passive"))
    )
    (net (code "106") (name "unconnected-(U800-PD15-Pad105)") (class "Default")
      (node (ref "U800") (pin "105") (pinfunction "PD15_105") (pintype "passive"))
    )
    (net (code "107") (name "unconnected-(U800-PE0-Pad169)") (class "Default")
      (node (ref "U800") (pin "169") (pinfunction "PE0_169") (pintype "passive"))
    )
    (net (code "108") (name "unconnected-(U800-PE1-Pad170)") (class "Default")
      (node (ref "U800") (pin "170") (pinfunction "PE1_170") (pintype "passive"))
    )
    (net (code "109") (name "unconnected-(U800-PE3-Pad2)") (class "Default")
      (node (ref "U800") (pin "2") (pinfunction "PE3_2") (pintype "passive"))
    )
    (net (code "110") (name "unconnected-(U800-PE4-Pad3)") (class "Default")
      (node (ref "U800") (pin "3") (pinfunction "PE4_3") (pintype "passive"))
    )
    (net (code "111") (name "unconnected-(U800-PE5-Pad4)") (class "Default")
      (node (ref "U800") (pin "4") (pinfunction "PE5_4") (pintype "passive"))
    )
    (net (code "112") (name "unconnected-(U800-PE6-Pad5)") (class "Default")
      (node (ref "U800") (pin "5") (pinfunction "PE6_5") (pintype "passive"))
    )
    (net (code "113") (name "unconnected-(U800-PE7-Pad68)") (class "Default")
      (node (ref "U800") (pin "68") (pinfunction "PE7_68") (pintype "passive"))
    )
    (net (code "114") (name "unconnected-(U800-PE8-Pad69)") (class "Default")
      (node (ref "U800") (pin "69") (pinfunction "PE8_69") (pintype "passive"))
    )
    (net (code "115") (name "unconnected-(U800-PE12-Pad75)") (class "Default")
      (node (ref "U800") (pin "75") (pinfunction "PE12_75") (pintype "passive"))
    )
    (net (code "116") (name "unconnected-(U800-PE13-Pad76)") (class "Default")
      (node (ref "U800") (pin "76") (pinfunction "PE13_76") (pintype "passive"))
    )
    (net (code "117") (name "unconnected-(U800-PE14-Pad77)") (class "Default")
      (node (ref "U800") (pin "77") (pinfunction "PE14_77") (pintype "passive"))
    )
    (net (code "118") (name "unconnected-(U800-PE15-Pad78)") (class "Default")
      (node (ref "U800") (pin "78") (pinfunction "PE15_78") (pintype "passive"))
    )
    (net (code "119") (name "unconnected-(U800-PF7-Pad25)") (class "Default")
      (node (ref "U800") (pin "25") (pinfunction "PF7_25") (pintype "passive"))
    )
    (net (code "120") (name "unconnected-(U800-PF11-Pad59)") (class "Default")
      (node (ref "U800") (pin "59") (pinfunction "PF11_59") (pintype "passive"))
    )
    (net (code "121") (name "unconnected-(U800-PF12-Pad60)") (class "Default")
      (node (ref "U800") (pin "60") (pinfunction "PF12_60") (pintype "passive"))
    )
    (net (code "122") (name "unconnected-(U800-PF13-Pad63)") (class "Default")
      (node (ref "U800") (pin "63") (pinfunction "PF13_63") (pintype "passive"))
    )
    (net (code "123") (name "unconnected-(U800-PF14-Pad64)") (class "Default")
      (node (ref "U800") (pin "64") (pinfunction "PF14_64") (pintype "passive"))
    )
    (net (code "124") (name "unconnected-(U800-PF15-Pad65)") (class "Default")
      (node (ref "U800") (pin "65") (pinfunction "PF15_65") (pintype "passive"))
    )
    (net (code "125") (name "unconnected-(U800-PG0-Pad66)") (class "Default")
      (node (ref "U800") (pin "66") (pinfunction "PG0_66") (pintype "passive"))
    )
    (net (code "126") (name "unconnected-(U800-PG1-Pad67)") (class "Default")
      (node (ref "U800") (pin "67") (pinfunction "PG1_67") (pintype "passive"))
    )
    (net (code "127") (name "unconnected-(U800-PG2-Pad106)") (class "Default")
      (node (ref "U800") (pin "106") (pinfunction "PG2_106") (pintype "passive"))
    )
    (net (code "128") (name "unconnected-(U800-PG3-Pad107)") (class "Default")
      (node (ref "U800") (pin "107") (pinfunction "PG3_107") (pintype "passive"))
    )
    (net (code "129") (name "unconnected-(U800-PG4-Pad108)") (class "Default")
      (node (ref "U800") (pin "108") (pinfunction "PG4_108") (pintype "passive"))
    )
    (net (code "130") (name "unconnected-(U800-PG10-Pad153)") (class "Default")
      (node (ref "U800") (pin "153") (pinfunction "PG10_153") (pintype "passive"))
    )
    (net (code "131") (name "unconnected-(U800-PG11-Pad154)") (class "Default")
      (node (ref "U800") (pin "154") (pinfunction "PG11_154") (pintype "passive"))
    )
    (net (code "132") (name "unconnected-(U800-PG12-Pad155)") (class "Default")
      (node (ref "U800") (pin "155") (pinfunction "PG12_155") (pintype "passive"))
    )
    (net (code "133") (name "unconnected-(U800-PG13-Pad156)") (class "Default")
      (node (ref "U800") (pin "156") (pinfunction "PG13_156") (pintype "passive"))
    )
    (net (code "134") (name "unconnected-(U800-PG14-Pad157)") (class "Default")
      (node (ref "U800") (pin "157") (pinfunction "PG14_157") (pintype "passive"))
    )
    (net (code "135") (name "unconnected-(U800-PG15-Pad160)") (class "Default")
      (node (ref "U800") (pin "160") (pinfunction "PG15_160") (pintype "passive"))
    )
    (net (code "136") (name "unconnected-(U800-PH4-Pad45)") (class "Default")
      (node (ref "U800") (pin "45") (pinfunction "PH4_45") (pintype "passive"))
    )
    (net (code "137") (name "unconnected-(U800-PH5-Pad46)") (class "Default")
      (node (ref "U800") (pin "46") (pinfunction "PH5_46") (pintype "passive"))
    )
    (net (code "138") (name "unconnected-(U800-PH6-Pad83)") (class "Default")
      (node (ref "U800") (pin "83") (pinfunction "PH6_83") (pintype "passive"))
    )
    (net (code "139") (name "unconnected-(U800-PH7-Pad84)") (class "Default")
      (node (ref "U800") (pin "84") (pinfunction "PH7_84") (pintype "passive"))
    )
    (net (code "140") (name "unconnected-(U800-PH8-Pad85)") (class "Default")
      (node (ref "U800") (pin "85") (pinfunction "PH8_85") (pintype "passive"))
    )
    (net (code "141") (name "unconnected-(U800-PH9-Pad86)") (class "Default")
      (node (ref "U800") (pin "86") (pinfunction "PH9_86") (pintype "passive"))
    )
    (net (code "142") (name "unconnected-(U800-PH13-Pad128)") (class "Default")
      (node (ref "U800") (pin "128") (pinfunction "PH13_128") (pintype "passive"))
    )
    (net (code "143") (name "unconnected-(U800-PH14-Pad129)") (class "Default")
      (node (ref "U800") (pin "129") (pinfunction "PH14_129") (pintype "passive"))
    )
    (net (code "144") (name "unconnected-(U800-PH15-Pad130)") (class "Default")
      (node (ref "U800") (pin "130") (pinfunction "PH15_130") (pintype "passive"))
    )
    (net (code "145") (name "unconnected-(U800-PI0-Pad131)") (class "Default")
      (node (ref "U800") (pin "131") (pinfunction "PI0_131") (pintype "passive"))
    )
    (net (code "146") (name "unconnected-(U800-PI1-Pad132)") (class "Default")
      (node (ref "U800") (pin "132") (pinfunction "PI1_132") (pintype "passive"))
    )
    (net (code "147") (name "unconnected-(U800-PI2-Pad133)") (class "Default")
      (node (ref "U800") (pin "133") (pinfunction "PI2_133") (pintype "passive"))
    )
    (net (code "148") (name "unconnected-(U800-PI3-Pad134)") (class "Default")
      (node (ref "U800") (pin "134") (pinfunction "PI3_134") (pintype "passive"))
    )
    (net (code "149") (name "unconnected-(U800-PI4-Pad173)") (class "Default")
      (node (ref "U800") (pin "173") (pinfunction "PI4_173") (pintype "passive"))
    )
    (net (code "150") (name "unconnected-(U800-PI5-Pad174)") (class "Default")
      (node (ref "U800") (pin "174") (pinfunction "PI5_174") (pintype "passive"))
    )
    (net (code "151") (name "unconnected-(U800-PI6-Pad175)") (class "Default")
      (node (ref "U800") (pin "175") (pinfunction "PI6_175") (pintype "passive"))
    )
    (net (code "152") (name "unconnected-(U800-PI7-Pad176)") (class "Default")
      (node (ref "U800") (pin "176") (pinfunction "PI7_176") (pintype "passive"))
    )
    (net (code "153") (name "unconnected-(U800-PI8-Pad7)") (class "Default")
      (node (ref "U800") (pin "7") (pinfunction "PI8_7") (pintype "passive"))
    )
    (net (code "154") (name "unconnected-(U800-PI9-Pad11)") (class "Default")
      (node (ref "U800") (pin "11") (pinfunction "PI9_11") (pintype "passive"))
    )
    (net (code "155") (name "unconnected-(U800-PI10-Pad12)") (class "Default")
      (node (ref "U800") (pin "12") (pinfunction "PI10_12") (pintype "passive"))
    )
    (net (code "156") (name "unconnected-(U800-PI11-Pad13)") (class "Default")
      (node (ref "U800") (pin "13") (pinfunction "PI11_13") (pintype "passive"))
    )
  )
)
